# e-Tapperhandpiece21.net
KiCad netlist of a schematic drawn in EAGLE
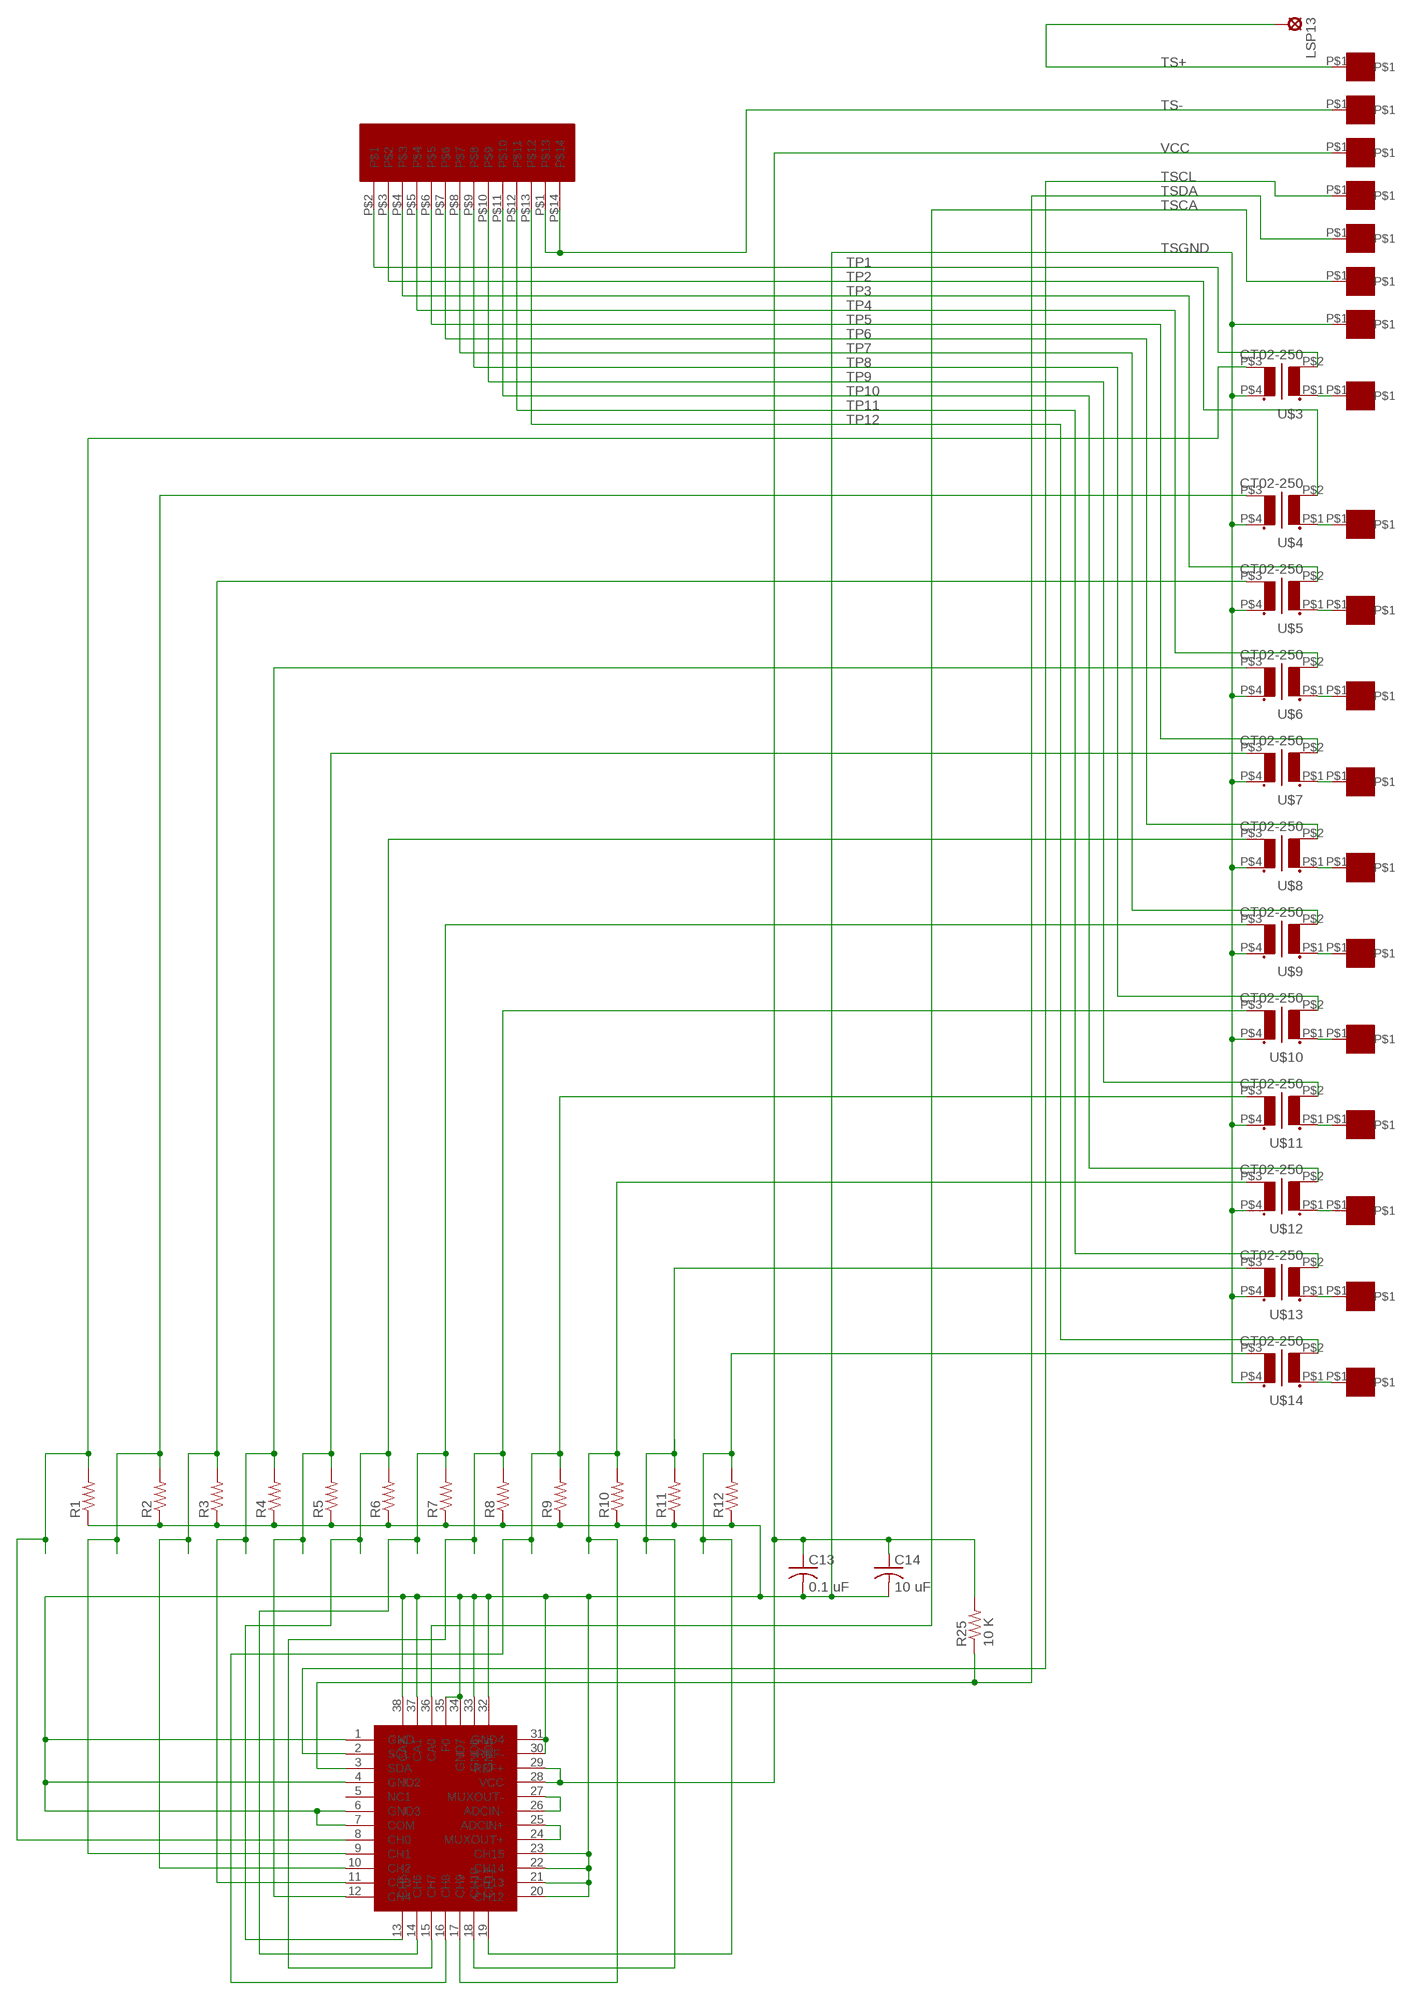
[diagram p0: schematic, sheet 1]

(export (version "E")
  (design (tool "Eeschema 10.0.6"))
  (components
    (comp (ref "C13")
      (value "0.1 uF")
      (footprint "eagle-import:C0603")
      (libsource (lib "eagle-import") (part "C-USC0603"))
    )
    (comp (ref "C14")
      (value "10 uF")
      (footprint "eagle-import:C0805")
      (libsource (lib "eagle-import") (part "C-USC0805"))
    )
    (comp (ref "LSP13")
      (value "SE11")
      (footprint "eagle-import:SE11")
      (libsource (lib "eagle-import") (part "SE11"))
    )
    (comp (ref "R1")
      (value "R-US_R0402")
      (footprint "eagle-import:R0402")
      (libsource (lib "eagle-import") (part "R-US_R0402"))
    )
    (comp (ref "R2")
      (value "R-US_R0402")
      (footprint "eagle-import:R0402")
      (libsource (lib "eagle-import") (part "R-US_R0402"))
    )
    (comp (ref "R3")
      (value "R-US_R0402")
      (footprint "eagle-import:R0402")
      (libsource (lib "eagle-import") (part "R-US_R0402"))
    )
    (comp (ref "R4")
      (value "R-US_R0402")
      (footprint "eagle-import:R0402")
      (libsource (lib "eagle-import") (part "R-US_R0402"))
    )
    (comp (ref "R5")
      (value "R-US_R0402")
      (footprint "eagle-import:R0402")
      (libsource (lib "eagle-import") (part "R-US_R0402"))
    )
    (comp (ref "R6")
      (value "R-US_R0402")
      (footprint "eagle-import:R0402")
      (libsource (lib "eagle-import") (part "R-US_R0402"))
    )
    (comp (ref "R7")
      (value "R-US_R0402")
      (footprint "eagle-import:R0402")
      (libsource (lib "eagle-import") (part "R-US_R0402"))
    )
    (comp (ref "R8")
      (value "R-US_R0402")
      (footprint "eagle-import:R0402")
      (libsource (lib "eagle-import") (part "R-US_R0402"))
    )
    (comp (ref "R9")
      (value "R-US_R0402")
      (footprint "eagle-import:R0402")
      (libsource (lib "eagle-import") (part "R-US_R0402"))
    )
    (comp (ref "R10")
      (value "R-US_R0402")
      (footprint "eagle-import:R0402")
      (libsource (lib "eagle-import") (part "R-US_R0402"))
    )
    (comp (ref "R11")
      (value "R-US_R0402")
      (footprint "eagle-import:R0402")
      (libsource (lib "eagle-import") (part "R-US_R0402"))
    )
    (comp (ref "R12")
      (value "R-US_R0402")
      (footprint "eagle-import:R0402")
      (libsource (lib "eagle-import") (part "R-US_R0402"))
    )
    (comp (ref "R25")
      (value "10 K")
      (footprint "eagle-import:R0402")
      (libsource (lib "eagle-import") (part "R-US_R0402"))
    )
    (comp (ref "TSP1")
      (value "ET1")
      (footprint "eagle-import:ET1")
      (libsource (lib "eagle-import") (part "ET1"))
    )
    (comp (ref "TSP2")
      (value "ET1")
      (footprint "eagle-import:ET1")
      (libsource (lib "eagle-import") (part "ET1"))
    )
    (comp (ref "TSP3")
      (value "ET1")
      (footprint "eagle-import:ET1")
      (libsource (lib "eagle-import") (part "ET1"))
    )
    (comp (ref "TSP4")
      (value "ET1")
      (footprint "eagle-import:ET1")
      (libsource (lib "eagle-import") (part "ET1"))
    )
    (comp (ref "TSP5")
      (value "ET1")
      (footprint "eagle-import:ET1")
      (libsource (lib "eagle-import") (part "ET1"))
    )
    (comp (ref "TSP6")
      (value "ET1")
      (footprint "eagle-import:ET1")
      (libsource (lib "eagle-import") (part "ET1"))
    )
    (comp (ref "TSP7")
      (value "ET1")
      (footprint "eagle-import:ET1")
      (libsource (lib "eagle-import") (part "ET1"))
    )
    (comp (ref "TSP8")
      (value "ET1")
      (footprint "eagle-import:ET1")
      (libsource (lib "eagle-import") (part "ET1"))
    )
    (comp (ref "TSP9")
      (value "ET1")
      (footprint "eagle-import:ET1")
      (libsource (lib "eagle-import") (part "ET1"))
    )
    (comp (ref "TSP10")
      (value "ET1")
      (footprint "eagle-import:ET1")
      (libsource (lib "eagle-import") (part "ET1"))
    )
    (comp (ref "TSP11")
      (value "ET1")
      (footprint "eagle-import:ET1")
      (libsource (lib "eagle-import") (part "ET1"))
    )
    (comp (ref "TSP12")
      (value "ET1")
      (footprint "eagle-import:ET1")
      (libsource (lib "eagle-import") (part "ET1"))
    )
    (comp (ref "TSP13")
      (value "ET1")
      (footprint "eagle-import:ET1")
      (libsource (lib "eagle-import") (part "ET1"))
    )
    (comp (ref "TSP14")
      (value "ET1")
      (footprint "eagle-import:ET1")
      (libsource (lib "eagle-import") (part "ET1"))
    )
    (comp (ref "TSP15")
      (value "ET1")
      (footprint "eagle-import:ET1")
      (libsource (lib "eagle-import") (part "ET1"))
    )
    (comp (ref "TSP16")
      (value "ET1")
      (footprint "eagle-import:ET1")
      (libsource (lib "eagle-import") (part "ET1"))
    )
    (comp (ref "TSP17")
      (value "ET1")
      (footprint "eagle-import:ET1")
      (libsource (lib "eagle-import") (part "ET1"))
    )
    (comp (ref "TSP18")
      (value "ET1")
      (footprint "eagle-import:ET1")
      (libsource (lib "eagle-import") (part "ET1"))
    )
    (comp (ref "TSP19")
      (value "ET1")
      (footprint "eagle-import:ET1")
      (libsource (lib "eagle-import") (part "ET1"))
    )
    (comp (ref "U$1")
      (value "LTC2497")
      (footprint "eagle-import:QFN38-5X7")
      (libsource (lib "eagle-import") (part "LTC2497"))
    )
    (comp (ref "U$2")
      (value "SS112D01")
      (footprint "eagle-import:SS112D01")
      (libsource (lib "eagle-import") (part "SS112D01"))
    )
    (comp (ref "U$3")
      (value "CT02-250")
      (footprint "eagle-import:CT02-250")
      (libsource (lib "eagle-import") (part "CT02-250"))
    )
    (comp (ref "U$4")
      (value "CT02-250")
      (footprint "eagle-import:CT02-250")
      (libsource (lib "eagle-import") (part "CT02-250"))
    )
    (comp (ref "U$5")
      (value "CT02-250")
      (footprint "eagle-import:CT02-250")
      (libsource (lib "eagle-import") (part "CT02-250"))
    )
    (comp (ref "U$6")
      (value "CT02-250")
      (footprint "eagle-import:CT02-250")
      (libsource (lib "eagle-import") (part "CT02-250"))
    )
    (comp (ref "U$7")
      (value "CT02-250")
      (footprint "eagle-import:CT02-250")
      (libsource (lib "eagle-import") (part "CT02-250"))
    )
    (comp (ref "U$8")
      (value "CT02-250")
      (footprint "eagle-import:CT02-250")
      (libsource (lib "eagle-import") (part "CT02-250"))
    )
    (comp (ref "U$9")
      (value "CT02-250")
      (footprint "eagle-import:CT02-250")
      (libsource (lib "eagle-import") (part "CT02-250"))
    )
    (comp (ref "U$10")
      (value "CT02-250")
      (footprint "eagle-import:CT02-250")
      (libsource (lib "eagle-import") (part "CT02-250"))
    )
    (comp (ref "U$11")
      (value "CT02-250")
      (footprint "eagle-import:CT02-250")
      (libsource (lib "eagle-import") (part "CT02-250"))
    )
    (comp (ref "U$12")
      (value "CT02-250")
      (footprint "eagle-import:CT02-250")
      (libsource (lib "eagle-import") (part "CT02-250"))
    )
    (comp (ref "U$13")
      (value "CT02-250")
      (footprint "eagle-import:CT02-250")
      (libsource (lib "eagle-import") (part "CT02-250"))
    )
    (comp (ref "U$14")
      (value "CT02-250")
      (footprint "eagle-import:CT02-250")
      (libsource (lib "eagle-import") (part "CT02-250"))
    )
  )
  (nets
    (net (code "1") (name "/TP1") (class "Default")
      (node (ref "U$2") (pin "P$2") (pinfunction "P$1_P$2") (pintype "bidirectional"))
      (node (ref "U$3") (pin "P$2") (pinfunction "P2_P$2") (pintype "passive"))
    )
    (net (code "2") (name "/TP2") (class "Default")
      (node (ref "U$2") (pin "P$3") (pinfunction "P$2_P$3") (pintype "bidirectional"))
      (node (ref "U$4") (pin "P$2") (pinfunction "P2_P$2") (pintype "passive"))
    )
    (net (code "3") (name "/TP3") (class "Default")
      (node (ref "U$2") (pin "P$4") (pinfunction "P$3_P$4") (pintype "bidirectional"))
      (node (ref "U$5") (pin "P$2") (pinfunction "P2_P$2") (pintype "passive"))
    )
    (net (code "4") (name "/TP4") (class "Default")
      (node (ref "U$2") (pin "P$5") (pinfunction "P$4_P$5") (pintype "bidirectional"))
      (node (ref "U$6") (pin "P$2") (pinfunction "P2_P$2") (pintype "passive"))
    )
    (net (code "5") (name "/TP5") (class "Default")
      (node (ref "U$2") (pin "P$6") (pinfunction "P$5_P$6") (pintype "bidirectional"))
      (node (ref "U$7") (pin "P$2") (pinfunction "P2_P$2") (pintype "passive"))
    )
    (net (code "6") (name "/TP6") (class "Default")
      (node (ref "U$2") (pin "P$7") (pinfunction "P$6_P$7") (pintype "bidirectional"))
      (node (ref "U$8") (pin "P$2") (pinfunction "P2_P$2") (pintype "passive"))
    )
    (net (code "7") (name "/TP7") (class "Default")
      (node (ref "U$2") (pin "P$8") (pinfunction "P$7_P$8") (pintype "bidirectional"))
      (node (ref "U$9") (pin "P$2") (pinfunction "P2_P$2") (pintype "passive"))
    )
    (net (code "8") (name "/TP8") (class "Default")
      (node (ref "U$10") (pin "P$2") (pinfunction "P2_P$2") (pintype "passive"))
      (node (ref "U$2") (pin "P$9") (pinfunction "P$8_P$9") (pintype "bidirectional"))
    )
    (net (code "9") (name "/TP9") (class "Default")
      (node (ref "U$11") (pin "P$2") (pinfunction "P2_P$2") (pintype "passive"))
      (node (ref "U$2") (pin "P$10") (pinfunction "P$9_P$10") (pintype "bidirectional"))
    )
    (net (code "10") (name "/TP10") (class "Default")
      (node (ref "U$12") (pin "P$2") (pinfunction "P2_P$2") (pintype "passive"))
      (node (ref "U$2") (pin "P$11") (pinfunction "P$10_P$11") (pintype "bidirectional"))
    )
    (net (code "11") (name "/TP11") (class "Default")
      (node (ref "U$13") (pin "P$2") (pinfunction "P2_P$2") (pintype "passive"))
      (node (ref "U$2") (pin "P$12") (pinfunction "P$11_P$12") (pintype "bidirectional"))
    )
    (net (code "12") (name "/TP12") (class "Default")
      (node (ref "U$14") (pin "P$2") (pinfunction "P2_P$2") (pintype "passive"))
      (node (ref "U$2") (pin "P$13") (pinfunction "P$12_P$13") (pintype "bidirectional"))
    )
    (net (code "13") (name "/TS+") (class "Default")
      (node (ref "LSP13") (pin "MP") (pinfunction "MP_MP") (pintype "passive"))
      (node (ref "TSP13") (pin "P$1") (pinfunction "P$1_P$1") (pintype "bidirectional"))
    )
    (net (code "14") (name "/TS-") (class "Default")
      (node (ref "TSP14") (pin "P$1") (pinfunction "P$1_P$1") (pintype "bidirectional"))
      (node (ref "U$2") (pin "P$1") (pinfunction "P$13_P$1") (pintype "bidirectional"))
      (node (ref "U$2") (pin "P$14") (pinfunction "P$14_P$14") (pintype "bidirectional"))
    )
    (net (code "15") (name "/TSCA") (class "Default")
      (node (ref "TSP18") (pin "P$1") (pinfunction "P$1_P$1") (pintype "bidirectional"))
      (node (ref "U$1") (pin "36") (pinfunction "CA0_36") (pintype "bidirectional"))
    )
    (net (code "16") (name "/TSCL") (class "Default")
      (node (ref "TSP16") (pin "P$1") (pinfunction "P$1_P$1") (pintype "bidirectional"))
      (node (ref "U$1") (pin "2") (pinfunction "SCL_2") (pintype "bidirectional"))
    )
    (net (code "17") (name "/TSDA") (class "Default")
      (node (ref "R25") (pin "1") (pinfunction "1_1") (pintype "passive"))
      (node (ref "TSP17") (pin "P$1") (pinfunction "P$1_P$1") (pintype "bidirectional"))
      (node (ref "U$1") (pin "3") (pinfunction "SDA_3") (pintype "bidirectional"))
    )
    (net (code "18") (name "/TSGND") (class "Default")
      (node (ref "C13") (pin "2") (pinfunction "2_2") (pintype "passive"))
      (node (ref "C14") (pin "2") (pinfunction "2_2") (pintype "passive"))
      (node (ref "R1") (pin "1") (pinfunction "1_1") (pintype "passive"))
      (node (ref "R10") (pin "1") (pinfunction "1_1") (pintype "passive"))
      (node (ref "R11") (pin "1") (pinfunction "1_1") (pintype "passive"))
      (node (ref "R12") (pin "1") (pinfunction "1_1") (pintype "passive"))
      (node (ref "R2") (pin "1") (pinfunction "1_1") (pintype "passive"))
      (node (ref "R3") (pin "1") (pinfunction "1_1") (pintype "passive"))
      (node (ref "R4") (pin "1") (pinfunction "1_1") (pintype "passive"))
      (node (ref "R5") (pin "1") (pinfunction "1_1") (pintype "passive"))
      (node (ref "R6") (pin "1") (pinfunction "1_1") (pintype "passive"))
      (node (ref "R7") (pin "1") (pinfunction "1_1") (pintype "passive"))
      (node (ref "R8") (pin "1") (pinfunction "1_1") (pintype "passive"))
      (node (ref "R9") (pin "1") (pinfunction "1_1") (pintype "passive"))
      (node (ref "TSP19") (pin "P$1") (pinfunction "P$1_P$1") (pintype "bidirectional"))
      (node (ref "U$1") (pin "1") (pinfunction "GND_1") (pintype "power_in"))
      (node (ref "U$1") (pin "20") (pinfunction "CH12_20") (pintype "input"))
      (node (ref "U$1") (pin "21") (pinfunction "CH13_21") (pintype "input"))
      (node (ref "U$1") (pin "22") (pinfunction "CH14_22") (pintype "input"))
      (node (ref "U$1") (pin "23") (pinfunction "CH15_23") (pintype "input"))
      (node (ref "U$1") (pin "30") (pinfunction "REF-_30") (pintype "bidirectional"))
      (node (ref "U$1") (pin "31") (pinfunction "GND4_31") (pintype "power_in"))
      (node (ref "U$1") (pin "32") (pinfunction "GND5_32") (pintype "power_in"))
      (node (ref "U$1") (pin "33") (pinfunction "GND6_33") (pintype "power_in"))
      (node (ref "U$1") (pin "34") (pinfunction "GND7_34") (pintype "power_in"))
      (node (ref "U$1") (pin "35") (pinfunction "F0_35") (pintype "bidirectional"))
      (node (ref "U$1") (pin "37") (pinfunction "CA1_37") (pintype "bidirectional"))
      (node (ref "U$1") (pin "38") (pinfunction "CA2_38") (pintype "bidirectional"))
      (node (ref "U$1") (pin "4") (pinfunction "GND2_4") (pintype "power_in"))
      (node (ref "U$1") (pin "6") (pinfunction "GND3_6") (pintype "power_in"))
      (node (ref "U$1") (pin "7") (pinfunction "COM_7") (pintype "power_in"))
      (node (ref "U$10") (pin "P$4") (pinfunction "S1_P$4") (pintype "passive"))
      (node (ref "U$11") (pin "P$4") (pinfunction "S1_P$4") (pintype "passive"))
      (node (ref "U$12") (pin "P$4") (pinfunction "S1_P$4") (pintype "passive"))
      (node (ref "U$13") (pin "P$4") (pinfunction "S1_P$4") (pintype "passive"))
      (node (ref "U$14") (pin "P$4") (pinfunction "S1_P$4") (pintype "passive"))
      (node (ref "U$3") (pin "P$4") (pinfunction "S1_P$4") (pintype "passive"))
      (node (ref "U$4") (pin "P$4") (pinfunction "S1_P$4") (pintype "passive"))
      (node (ref "U$5") (pin "P$4") (pinfunction "S1_P$4") (pintype "passive"))
      (node (ref "U$6") (pin "P$4") (pinfunction "S1_P$4") (pintype "passive"))
      (node (ref "U$7") (pin "P$4") (pinfunction "S1_P$4") (pintype "passive"))
      (node (ref "U$8") (pin "P$4") (pinfunction "S1_P$4") (pintype "passive"))
      (node (ref "U$9") (pin "P$4") (pinfunction "S1_P$4") (pintype "passive"))
    )
    (net (code "19") (name "/VCC") (class "Default")
      (node (ref "C13") (pin "1") (pinfunction "1_1") (pintype "passive"))
      (node (ref "C14") (pin "1") (pinfunction "1_1") (pintype "passive"))
      (node (ref "R25") (pin "2") (pinfunction "2_2") (pintype "passive"))
      (node (ref "TSP15") (pin "P$1") (pinfunction "P$1_P$1") (pintype "bidirectional"))
      (node (ref "U$1") (pin "28") (pinfunction "VCC_28") (pintype "power_in"))
      (node (ref "U$1") (pin "29") (pinfunction "REF+_29") (pintype "bidirectional"))
    )
    (net (code "20") (name "Net-(U$1-ADCIN+)") (class "Default")
      (node (ref "U$1") (pin "24") (pinfunction "MUXOUT+_24") (pintype "bidirectional"))
      (node (ref "U$1") (pin "25") (pinfunction "ADCIN+_25") (pintype "bidirectional"))
    )
    (net (code "21") (name "Net-(U$1-ADCIN-)") (class "Default")
      (node (ref "U$1") (pin "26") (pinfunction "ADCIN-_26") (pintype "bidirectional"))
      (node (ref "U$1") (pin "27") (pinfunction "MUXOUT-_27") (pintype "bidirectional"))
    )
    (net (code "22") (name "Net-(U$1-CH0)") (class "Default")
      (node (ref "R1") (pin "2") (pinfunction "2_2") (pintype "passive"))
      (node (ref "U$1") (pin "8") (pinfunction "CH0_8") (pintype "input"))
      (node (ref "U$3") (pin "P$3") (pinfunction "S2_P$3") (pintype "passive"))
    )
    (net (code "23") (name "Net-(U$1-CH1)") (class "Default")
      (node (ref "R2") (pin "2") (pinfunction "2_2") (pintype "passive"))
      (node (ref "U$1") (pin "9") (pinfunction "CH1_9") (pintype "input"))
      (node (ref "U$4") (pin "P$3") (pinfunction "S2_P$3") (pintype "passive"))
    )
    (net (code "24") (name "Net-(U$1-CH2)") (class "Default")
      (node (ref "R3") (pin "2") (pinfunction "2_2") (pintype "passive"))
      (node (ref "U$1") (pin "10") (pinfunction "CH2_10") (pintype "input"))
      (node (ref "U$5") (pin "P$3") (pinfunction "S2_P$3") (pintype "passive"))
    )
    (net (code "25") (name "Net-(U$1-CH3)") (class "Default")
      (node (ref "R4") (pin "2") (pinfunction "2_2") (pintype "passive"))
      (node (ref "U$1") (pin "11") (pinfunction "CH3_11") (pintype "input"))
      (node (ref "U$6") (pin "P$3") (pinfunction "S2_P$3") (pintype "passive"))
    )
    (net (code "26") (name "Net-(U$1-CH4)") (class "Default")
      (node (ref "R5") (pin "2") (pinfunction "2_2") (pintype "passive"))
      (node (ref "U$1") (pin "12") (pinfunction "CH4_12") (pintype "input"))
      (node (ref "U$7") (pin "P$3") (pinfunction "S2_P$3") (pintype "passive"))
    )
    (net (code "27") (name "Net-(U$1-CH5)") (class "Default")
      (node (ref "R6") (pin "2") (pinfunction "2_2") (pintype "passive"))
      (node (ref "U$1") (pin "13") (pinfunction "CH5_13") (pintype "input"))
      (node (ref "U$8") (pin "P$3") (pinfunction "S2_P$3") (pintype "passive"))
    )
    (net (code "28") (name "Net-(U$1-CH6)") (class "Default")
      (node (ref "R7") (pin "2") (pinfunction "2_2") (pintype "passive"))
      (node (ref "U$1") (pin "14") (pinfunction "CH6_14") (pintype "input"))
      (node (ref "U$9") (pin "P$3") (pinfunction "S2_P$3") (pintype "passive"))
    )
    (net (code "29") (name "Net-(U$1-CH7)") (class "Default")
      (node (ref "R8") (pin "2") (pinfunction "2_2") (pintype "passive"))
      (node (ref "U$1") (pin "15") (pinfunction "CH7_15") (pintype "input"))
      (node (ref "U$10") (pin "P$3") (pinfunction "S2_P$3") (pintype "passive"))
    )
    (net (code "30") (name "Net-(U$1-CH8)") (class "Default")
      (node (ref "R9") (pin "2") (pinfunction "2_2") (pintype "passive"))
      (node (ref "U$1") (pin "16") (pinfunction "CH8_16") (pintype "input"))
      (node (ref "U$11") (pin "P$3") (pinfunction "S2_P$3") (pintype "passive"))
    )
    (net (code "31") (name "Net-(U$1-CH9)") (class "Default")
      (node (ref "R10") (pin "2") (pinfunction "2_2") (pintype "passive"))
      (node (ref "U$1") (pin "17") (pinfunction "CH9_17") (pintype "input"))
      (node (ref "U$12") (pin "P$3") (pinfunction "S2_P$3") (pintype "passive"))
    )
    (net (code "32") (name "Net-(U$1-CH10)") (class "Default")
      (node (ref "R11") (pin "2") (pinfunction "2_2") (pintype "passive"))
      (node (ref "U$1") (pin "18") (pinfunction "CH10_18") (pintype "input"))
      (node (ref "U$13") (pin "P$3") (pinfunction "S2_P$3") (pintype "passive"))
    )
    (net (code "33") (name "Net-(U$1-CH11)") (class "Default")
      (node (ref "R12") (pin "2") (pinfunction "2_2") (pintype "passive"))
      (node (ref "U$1") (pin "19") (pinfunction "CH11_19") (pintype "input"))
      (node (ref "U$14") (pin "P$3") (pinfunction "S2_P$3") (pintype "passive"))
    )
    (net (code "34") (name "Net-(U$3-P1)") (class "Default")
      (node (ref "TSP1") (pin "P$1") (pinfunction "P$1_P$1") (pintype "bidirectional"))
      (node (ref "U$3") (pin "P$1") (pinfunction "P1_P$1") (pintype "passive"))
    )
    (net (code "35") (name "Net-(U$4-P1)") (class "Default")
      (node (ref "TSP2") (pin "P$1") (pinfunction "P$1_P$1") (pintype "bidirectional"))
      (node (ref "U$4") (pin "P$1") (pinfunction "P1_P$1") (pintype "passive"))
    )
    (net (code "36") (name "Net-(U$5-P1)") (class "Default")
      (node (ref "TSP3") (pin "P$1") (pinfunction "P$1_P$1") (pintype "bidirectional"))
      (node (ref "U$5") (pin "P$1") (pinfunction "P1_P$1") (pintype "passive"))
    )
    (net (code "37") (name "Net-(U$6-P1)") (class "Default")
      (node (ref "TSP4") (pin "P$1") (pinfunction "P$1_P$1") (pintype "bidirectional"))
      (node (ref "U$6") (pin "P$1") (pinfunction "P1_P$1") (pintype "passive"))
    )
    (net (code "38") (name "Net-(U$7-P1)") (class "Default")
      (node (ref "TSP5") (pin "P$1") (pinfunction "P$1_P$1") (pintype "bidirectional"))
      (node (ref "U$7") (pin "P$1") (pinfunction "P1_P$1") (pintype "passive"))
    )
    (net (code "39") (name "Net-(U$8-P1)") (class "Default")
      (node (ref "TSP6") (pin "P$1") (pinfunction "P$1_P$1") (pintype "bidirectional"))
      (node (ref "U$8") (pin "P$1") (pinfunction "P1_P$1") (pintype "passive"))
    )
    (net (code "40") (name "Net-(U$9-P1)") (class "Default")
      (node (ref "TSP7") (pin "P$1") (pinfunction "P$1_P$1") (pintype "bidirectional"))
      (node (ref "U$9") (pin "P$1") (pinfunction "P1_P$1") (pintype "passive"))
    )
    (net (code "41") (name "Net-(U$10-P1)") (class "Default")
      (node (ref "TSP8") (pin "P$1") (pinfunction "P$1_P$1") (pintype "bidirectional"))
      (node (ref "U$10") (pin "P$1") (pinfunction "P1_P$1") (pintype "passive"))
    )
    (net (code "42") (name "Net-(U$11-P1)") (class "Default")
      (node (ref "TSP9") (pin "P$1") (pinfunction "P$1_P$1") (pintype "bidirectional"))
      (node (ref "U$11") (pin "P$1") (pinfunction "P1_P$1") (pintype "passive"))
    )
    (net (code "43") (name "Net-(U$12-P1)") (class "Default")
      (node (ref "TSP10") (pin "P$1") (pinfunction "P$1_P$1") (pintype "bidirectional"))
      (node (ref "U$12") (pin "P$1") (pinfunction "P1_P$1") (pintype "passive"))
    )
    (net (code "44") (name "Net-(U$13-P1)") (class "Default")
      (node (ref "TSP11") (pin "P$1") (pinfunction "P$1_P$1") (pintype "bidirectional"))
      (node (ref "U$13") (pin "P$1") (pinfunction "P1_P$1") (pintype "passive"))
    )
    (net (code "45") (name "Net-(U$14-P1)") (class "Default")
      (node (ref "TSP12") (pin "P$1") (pinfunction "P$1_P$1") (pintype "bidirectional"))
      (node (ref "U$14") (pin "P$1") (pinfunction "P1_P$1") (pintype "passive"))
    )
    (net (code "46") (name "unconnected-(U$1-NC1-Pad5)") (class "Default")
      (node (ref "U$1") (pin "5") (pinfunction "NC1_5") (pintype "no_connect"))
    )
  )
)
